# tinybot.net
KiCad netlist of a schematic drawn in EAGLE
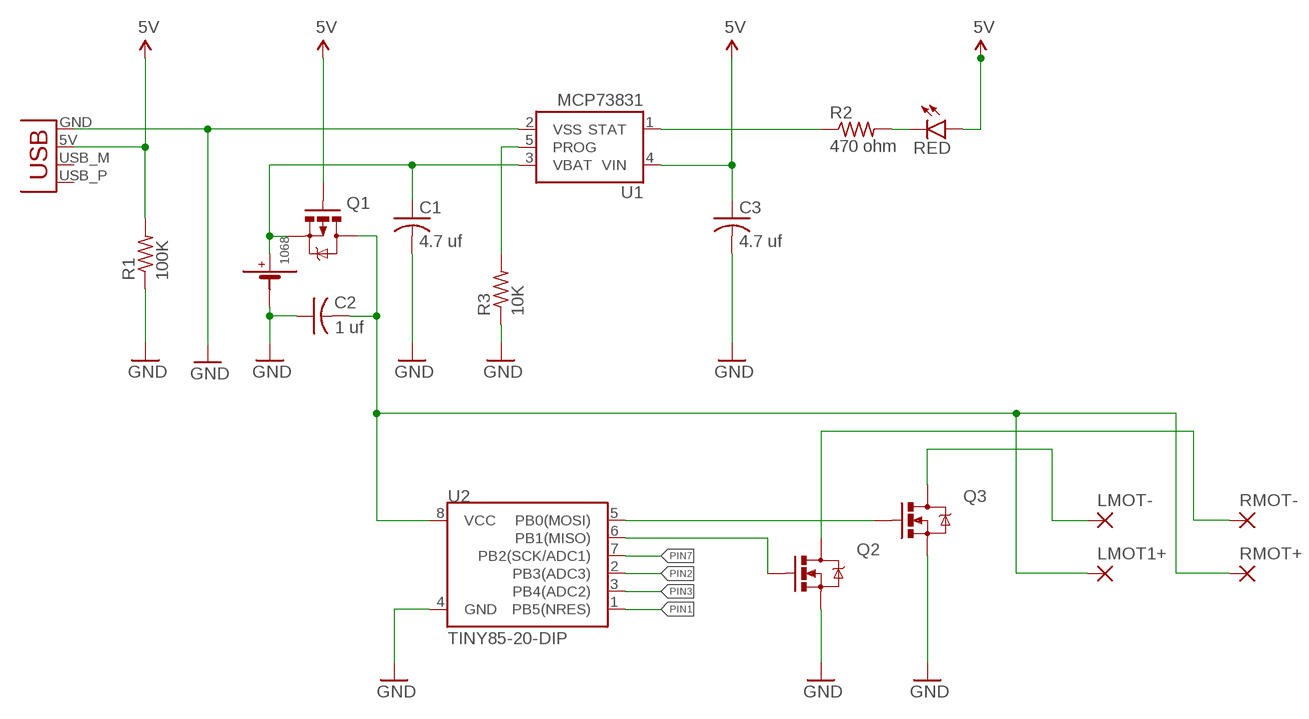
[diagram p0: schematic, sheet 1]

(export (version "E")
  (design (tool "Eeschema 10.0.6"))
  (components
    (comp (ref "C1")
      (value "4.7 uf")
      (footprint "eagle-import:C025-025X050")
      (libsource (lib "eagle-import") (part "C-US025-025X050"))
    )
    (comp (ref "C2")
      (value "1 uf")
      (footprint "eagle-import:C025-025X050")
      (libsource (lib "eagle-import") (part "C-US025-025X050"))
    )
    (comp (ref "C3")
      (value "4.7 uf")
      (footprint "eagle-import:C025-025X050")
      (libsource (lib "eagle-import") (part "C-US025-025X050"))
    )
    (comp (ref "JP1")
      (value "USBPCB")
      (footprint "eagle-import:USB-A-PCB")
      (libsource (lib "eagle-import") (part "USBPCB"))
    )
    (comp (ref "LMOT-")
      (value "WIREPADSMD1,27-254")
      (footprint "eagle-import:SMD1,27-2,54")
      (libsource (lib "eagle-import") (part "WIREPADSMD1,27-254"))
    )
    (comp (ref "LMOT1+")
      (value "WIREPADSMD1,27-254")
      (footprint "eagle-import:SMD1,27-2,54")
      (libsource (lib "eagle-import") (part "WIREPADSMD1,27-254"))
    )
    (comp (ref "Q1")
      (value "MOSFET-PCHANNEL")
      (footprint "eagle-import:SOT23-3")
      (libsource (lib "eagle-import") (part "MOSFET-PCHANNEL"))
    )
    (comp (ref "Q2")
      (value "2N7002PW")
      (footprint "eagle-import:SOT23")
      (libsource (lib "eagle-import") (part "MOSFET-NCHANNELBSS138"))
    )
    (comp (ref "Q3")
      (value "2N7002PW")
      (footprint "eagle-import:SOT23")
      (libsource (lib "eagle-import") (part "MOSFET-NCHANNELBSS138"))
    )
    (comp (ref "R1")
      (value "100K")
      (footprint "eagle-import:0204_5")
      (libsource (lib "eagle-import") (part "R-US_0204/5"))
    )
    (comp (ref "R2")
      (value "470 ohm")
      (footprint "eagle-import:0204_5")
      (libsource (lib "eagle-import") (part "R-US_0204/5"))
    )
    (comp (ref "R3")
      (value "10K")
      (footprint "eagle-import:0204_5")
      (libsource (lib "eagle-import") (part "R-US_0204/5"))
    )
    (comp (ref "RED")
      (value "LED3MM")
      (footprint "eagle-import:LED3MM")
      (libsource (lib "eagle-import") (part "LED3MM"))
    )
    (comp (ref "RMOT+")
      (value "WIREPADSMD1,27-254")
      (footprint "eagle-import:SMD1,27-2,54")
      (libsource (lib "eagle-import") (part "WIREPADSMD1,27-254"))
    )
    (comp (ref "RMOT-")
      (value "WIREPADSMD1,27-254")
      (footprint "eagle-import:SMD1,27-2,54")
      (libsource (lib "eagle-import") (part "WIREPADSMD1,27-254"))
    )
    (comp (ref "U$1")
      (value "1068")
      (footprint "eagle-import:KEYSTONE1068")
      (libsource (lib "eagle-import") (part "1068"))
    )
    (comp (ref "U1")
      (value "MCP73831")
      (footprint "eagle-import:SOT23-5")
      (libsource (lib "eagle-import") (part "MCP73831"))
    )
    (comp (ref "U2")
      (value "TINY85-20-DIP")
      (footprint "eagle-import:DIP08")
      (libsource (lib "eagle-import") (part "ATTINY45TINY85-20-DIP"))
    )
  )
  (nets
    (net (code "1") (name "5V") (class "Default")
      (node (ref "C3") (pin "1") (pinfunction "1_1") (pintype "passive"))
      (node (ref "JP1") (pin "5V") (pinfunction "VBUS_5V") (pintype "bidirectional"))
      (node (ref "Q1") (pin "1") (pinfunction "G_1") (pintype "passive"))
      (node (ref "R1") (pin "2") (pinfunction "2_2") (pintype "passive"))
      (node (ref "RED") (pin "A") (pinfunction "A_A") (pintype "passive"))
      (node (ref "U1") (pin "4") (pinfunction "VIN_4") (pintype "power_in"))
    )
    (net (code "2") (name "GND") (class "Default")
      (node (ref "C1") (pin "2") (pinfunction "2_2") (pintype "passive"))
      (node (ref "C2") (pin "1") (pinfunction "1_1") (pintype "passive"))
      (node (ref "C3") (pin "2") (pinfunction "2_2") (pintype "passive"))
      (node (ref "JP1") (pin "GND") (pinfunction "GND_GND") (pintype "bidirectional"))
      (node (ref "Q2") (pin "2") (pinfunction "S_2") (pintype "passive"))
      (node (ref "Q3") (pin "2") (pinfunction "S_2") (pintype "passive"))
      (node (ref "R1") (pin "1") (pinfunction "1_1") (pintype "passive"))
      (node (ref "R3") (pin "1") (pinfunction "1_1") (pintype "passive"))
      (node (ref "U$1") (pin "NEG") (pinfunction "-_NEG") (pintype "passive"))
      (node (ref "U1") (pin "2") (pinfunction "VSS_2") (pintype "power_in"))
      (node (ref "U2") (pin "4") (pinfunction "GND_4") (pintype "bidirectional"))
    )
    (net (code "3") (name "Net-(LMOT--P)") (class "Default")
      (node (ref "LMOT-") (pin "1") (pinfunction "P_1") (pintype "passive"))
      (node (ref "Q3") (pin "3") (pinfunction "D_3") (pintype "passive"))
    )
    (net (code "4") (name "Net-(LMOT1+-P)") (class "Default")
      (node (ref "C2") (pin "2") (pinfunction "2_2") (pintype "passive"))
      (node (ref "LMOT1+") (pin "1") (pinfunction "P_1") (pintype "passive"))
      (node (ref "Q1") (pin "3") (pinfunction "D_3") (pintype "passive"))
      (node (ref "RMOT+") (pin "1") (pinfunction "P_1") (pintype "passive"))
      (node (ref "U2") (pin "8") (pinfunction "VCC_8") (pintype "bidirectional"))
    )
    (net (code "5") (name "Net-(Q1-S)") (class "Default")
      (node (ref "C1") (pin "1") (pinfunction "1_1") (pintype "passive"))
      (node (ref "Q1") (pin "2") (pinfunction "S_2") (pintype "passive"))
      (node (ref "U$1") (pin "POS") (pinfunction "+_POS") (pintype "passive"))
      (node (ref "U1") (pin "3") (pinfunction "VBAT_3") (pintype "power_in"))
    )
    (net (code "6") (name "Net-(Q2-D)") (class "Default")
      (node (ref "Q2") (pin "3") (pinfunction "D_3") (pintype "passive"))
      (node (ref "RMOT-") (pin "1") (pinfunction "P_1") (pintype "passive"))
    )
    (net (code "7") (name "Net-(Q2-G)") (class "Default")
      (node (ref "Q2") (pin "1") (pinfunction "G_1") (pintype "passive"))
      (node (ref "U2") (pin "6") (pinfunction "PB1(MISO)_6") (pintype "bidirectional"))
    )
    (net (code "8") (name "Net-(Q3-G)") (class "Default")
      (node (ref "Q3") (pin "1") (pinfunction "G_1") (pintype "passive"))
      (node (ref "U2") (pin "5") (pinfunction "PB0(MOSI)_5") (pintype "bidirectional"))
    )
    (net (code "9") (name "Net-(RED-C)") (class "Default")
      (node (ref "R2") (pin "2") (pinfunction "2_2") (pintype "passive"))
      (node (ref "RED") (pin "K") (pinfunction "C_K") (pintype "passive"))
    )
    (net (code "10") (name "Net-(U1-PROG)") (class "Default")
      (node (ref "R3") (pin "2") (pinfunction "2_2") (pintype "passive"))
      (node (ref "U1") (pin "5") (pinfunction "PROG_5") (pintype "input"))
    )
    (net (code "11") (name "Net-(U1-STAT)") (class "Default")
      (node (ref "R2") (pin "1") (pinfunction "1_1") (pintype "passive"))
      (node (ref "U1") (pin "1") (pinfunction "STAT_1") (pintype "output"))
    )
    (net (code "12") (name "PIN1") (class "Default")
      (node (ref "U2") (pin "1") (pinfunction "PB5(NRES)_1") (pintype "bidirectional"))
    )
    (net (code "13") (name "PIN2") (class "Default")
      (node (ref "U2") (pin "2") (pinfunction "PB3(ADC3)_2") (pintype "bidirectional"))
    )
    (net (code "14") (name "PIN3") (class "Default")
      (node (ref "U2") (pin "3") (pinfunction "PB4(ADC2)_3") (pintype "bidirectional"))
    )
    (net (code "15") (name "PIN7") (class "Default")
      (node (ref "U2") (pin "7") (pinfunction "PB2(SCK/ADC1)_7") (pintype "bidirectional"))
    )
    (net (code "16") (name "unconnected-(JP1-D+-PadUSB_P)") (class "Default")
      (node (ref "JP1") (pin "USB_P") (pinfunction "D+_USB_P") (pintype "bidirectional"))
    )
    (net (code "17") (name "unconnected-(JP1-D--PadUSB_M)") (class "Default")
      (node (ref "JP1") (pin "USB_M") (pinfunction "D-_USB_M") (pintype "bidirectional"))
    )
  )
)
